# motion_sensor_circuit.net
KiCad netlist of a schematic drawn in Altium Designer
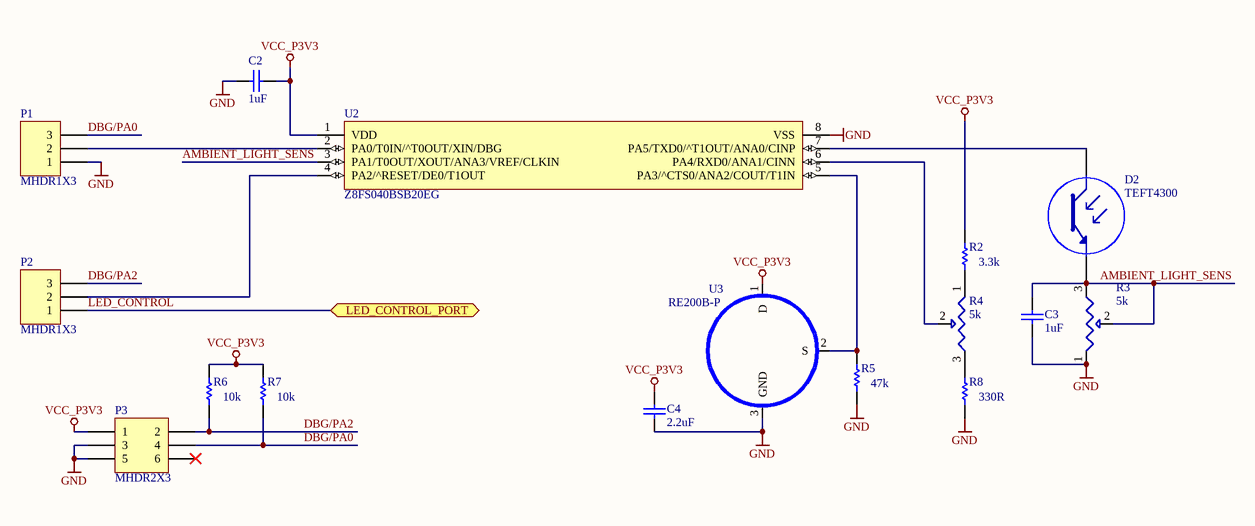
[diagram p0: motion sensor circuit.SchDoc]

(export (version "E")
  (design (tool "Eeschema 10.0.6"))
  (components
    (comp (ref "C2")
      (value "1uF")
      (footprint "1608[0603]")
      (description "Ceramic Chip Capacitor - Standard")
      (fields (field (name "Comment") "C0603C105K8PACTU") (field (name "PUBLISHER") "Altium Limited"))
      (libsource (lib "KEMET Chip Capacitor") (part "C0603"))
    )
    (comp (ref "C3")
      (value "1uF")
      (footprint "1608[0603]")
      (description "Ceramic Chip Capacitor - Standard")
      (fields (field (name "Comment") "C0603C105K8PACTU") (field (name "PUBLISHER") "Altium Limited"))
      (libsource (lib "KEMET Chip Capacitor") (part "C0603"))
    )
    (comp (ref "C4")
      (value "2.2uF")
      (footprint "1608[0603]")
      (description "Ceramic Chip Capacitor - Standard")
      (fields (field (name "Comment") "C0603C225K8PACTU") (field (name "PUBLISHER") "Altium Limited"))
      (libsource (lib "KEMET Chip Capacitor") (part "C0603"))
    )
    (comp (ref "D2")
      (value "TEFT4300")
      (footprint "LED")
      (description "Silicon NPN Phototransistor")
      (libsource (lib "Vishay Optoelectronics light sensors") (part "TEFT4300"))
    )
    (comp (ref "P1")
      (value "MHDR1X3")
      (footprint "MHDR1X3")
      (description "Header, 3-Pin")
      (fields (field (name "PUBLISHER") "Altium Limited"))
      (libsource (lib "Miscellaneous Connectors") (part "MHDR1X3"))
    )
    (comp (ref "P2")
      (value "MHDR1X3")
      (footprint "MHDR1X3")
      (description "Header, 3-Pin")
      (fields (field (name "PUBLISHER") "Altium Limited"))
      (libsource (lib "Miscellaneous Connectors") (part "MHDR1X3"))
    )
    (comp (ref "P3")
      (value "MHDR2X3")
      (footprint "MHDR2X3")
      (description "Header, 3-Pin, Dual row")
      (fields (field (name "PUBLISHER") "Altium Limited"))
      (libsource (lib "Miscellaneous Connectors") (part "MHDR2X3"))
    )
    (comp (ref "R2")
      (value "3.3k")
      (footprint "3-0603")
      (fields (field (name "Comment") "ERJ-3GEYJ332V") (field (name "PUBLISHER") "Altium Limited"))
      (libsource (lib "Panasonic Resistor") (part "ERJ3EK"))
    )
    (comp (ref "R3")
      (value "5k")
      (footprint "3386F")
      (description "3386 - 3/8 ” Square Trimpot Trimming Potentiometer")
      (fields (field (name "Comment") "3386F-1-502"))
      (libsource (lib "Bourns Variable Resistors") (part "3386F-1-XXX"))
    )
    (comp (ref "R4")
      (value "5k")
      (footprint "3386F")
      (description "3386 - 3/8 ” Square Trimpot Trimming Potentiometer")
      (fields (field (name "Comment") "3386F-1-502"))
      (libsource (lib "Bourns Variable Resistors") (part "3386F-1-XXX"))
    )
    (comp (ref "R5")
      (value "47k")
      (footprint "3-0603")
      (fields (field (name "Comment") "ERJ-3GEYJ473V") (field (name "PUBLISHER") "Altium Limited"))
      (libsource (lib "Panasonic Resistor") (part "ERJ3EK"))
    )
    (comp (ref "R6")
      (value "10k")
      (footprint "3-0603")
      (fields (field (name "Comment") "ERJ-3GEYJ103V") (field (name "PUBLISHER") "Altium Limited"))
      (libsource (lib "Panasonic Resistor") (part "ERJ3EK"))
    )
    (comp (ref "R7")
      (value "10k")
      (footprint "3-0603")
      (fields (field (name "Comment") "ERJ-3GEYJ103V") (field (name "PUBLISHER") "Altium Limited"))
      (libsource (lib "Panasonic Resistor") (part "ERJ3EK"))
    )
    (comp (ref "R8")
      (value "330R")
      (footprint "3-0603")
      (fields (field (name "Comment") "ERJ-3GEYJ331V") (field (name "PUBLISHER") "Altium Limited"))
      (libsource (lib "Panasonic Resistor") (part "ERJ3EK"))
    )
    (comp (ref "U2")
      (value "Z8FS040BSB20EG")
      (footprint "SOIC127P600X173-8N")
      (description "8-bit Microcontrollers - MCU ZMotion MCU Mot Det IC, 4KB Flash")
      (libsource (lib "Zilog Microcontroller 8-Bit") (part "Z8FS040BSB20EG"))
    )
    (comp (ref "U3")
      (value "RE200B-P")
      (footprint "RE200B-P")
      (description "Pyroelectric Passive Infrared Sensor")
      (libsource (lib "Rapid PIR sensors") (part "RE200B-P"))
    )
  )
  (nets
    (net (code "1") (name "/AMBIENT_LIGHT_SENS") (class "Default")
      (node (ref "C3") (pin "1") (pinfunction "1_1") (pintype "passive"))
      (node (ref "D2") (pin "2") (pintype "power_in"))
      (node (ref "R3") (pin "2") (pintype "power_in"))
      (node (ref "R3") (pin "3") (pinfunction "3_3") (pintype "power_in"))
      (node (ref "U2") (pin "3") (pinfunction "PA1/T0OUT/XOUT/ANA3/VREF/CLKIN_3") (pintype "bidirectional"))
    )
    (net (code "2") (name "/DBG{slash}PA0") (class "Default")
      (node (ref "P1") (pin "3") (pinfunction "3_3") (pintype "passive"))
      (node (ref "P3") (pin "4") (pinfunction "4_4") (pintype "passive"))
      (node (ref "R7") (pin "1") (pinfunction "1_1") (pintype "passive"))
    )
    (net (code "3") (name "/DBG{slash}PA2") (class "Default")
      (node (ref "P2") (pin "3") (pinfunction "3_3") (pintype "passive"))
      (node (ref "P3") (pin "2") (pinfunction "2_2") (pintype "passive"))
      (node (ref "R6") (pin "1") (pinfunction "1_1") (pintype "passive"))
    )
    (net (code "4") (name "/LED_CONTROL") (class "Default")
      (node (ref "P2") (pin "1") (pinfunction "1_1") (pintype "passive"))
    )
    (net (code "5") (name "GND") (class "Default")
      (node (ref "C2") (pin "2") (pinfunction "2_2") (pintype "passive"))
      (node (ref "C3") (pin "2") (pinfunction "2_2") (pintype "passive"))
      (node (ref "C4") (pin "2") (pinfunction "2_2") (pintype "passive"))
      (node (ref "P1") (pin "1") (pinfunction "1_1") (pintype "passive"))
      (node (ref "P3") (pin "3") (pinfunction "3_3") (pintype "passive"))
      (node (ref "P3") (pin "5") (pinfunction "5_5") (pintype "passive"))
      (node (ref "R3") (pin "1") (pintype "power_in"))
      (node (ref "R5") (pin "1") (pinfunction "1_1") (pintype "passive"))
      (node (ref "R8") (pin "1") (pinfunction "1_1") (pintype "passive"))
      (node (ref "U2") (pin "8") (pinfunction "VSS_8") (pintype "power_in"))
      (node (ref "U3") (pin "3") (pinfunction "GND_3") (pintype "power_in"))
    )
    (net (code "6") (name "Net-(R2-Pad1)") (class "Default")
      (node (ref "R2") (pin "1") (pinfunction "1_1") (pintype "passive"))
      (node (ref "R4") (pin "1") (pintype "power_in"))
    )
    (net (code "7") (name "Net-(R4-Pad3)") (class "Default")
      (node (ref "R4") (pin "3") (pinfunction "3_3") (pintype "power_in"))
      (node (ref "R8") (pin "2") (pinfunction "2_2") (pintype "passive"))
    )
    (net (code "8") (name "Net-(U2-PA0{slash}T0IN{slash}^T0OUT{slash}XIN{slash}DBG)") (class "Default")
      (node (ref "P1") (pin "2") (pinfunction "2_2") (pintype "passive"))
      (node (ref "U2") (pin "2") (pinfunction "PA0/T0IN/^T0OUT/XIN/DBG_2") (pintype "bidirectional"))
    )
    (net (code "9") (name "Net-(U2-PA2{slash}^RESET{slash}DE0{slash}T1OUT)") (class "Default")
      (node (ref "P2") (pin "2") (pinfunction "2_2") (pintype "passive"))
      (node (ref "U2") (pin "4") (pinfunction "PA2/^RESET/DE0/T1OUT_4") (pintype "bidirectional"))
    )
    (net (code "10") (name "Net-(U2-PA3{slash}^CTS0{slash}ANA2{slash}COUT{slash}T1IN)") (class "Default")
      (node (ref "R5") (pin "2") (pinfunction "2_2") (pintype "passive"))
      (node (ref "U2") (pin "5") (pinfunction "PA3/^CTS0/ANA2/COUT/T1IN_5") (pintype "bidirectional"))
      (node (ref "U3") (pin "2") (pinfunction "S_2") (pintype "power_in"))
    )
    (net (code "11") (name "Net-(U2-PA4{slash}RXD0{slash}ANA1{slash}CINN)") (class "Default")
      (node (ref "R4") (pin "2") (pintype "power_in"))
      (node (ref "U2") (pin "6") (pinfunction "PA4/RXD0/ANA1/CINN_6") (pintype "bidirectional"))
    )
    (net (code "12") (name "Net-(U2-PA5{slash}TXD0{slash}^T1OUT{slash}ANA0{slash}CINP)") (class "Default")
      (node (ref "D2") (pin "1") (pintype "power_in"))
      (node (ref "U2") (pin "7") (pinfunction "PA5/TXD0/^T1OUT/ANA0/CINP_7") (pintype "bidirectional"))
    )
    (net (code "13") (name "VCC_P3V3") (class "Default")
      (node (ref "C2") (pin "1") (pinfunction "1_1") (pintype "passive"))
      (node (ref "C4") (pin "1") (pinfunction "1_1") (pintype "passive"))
      (node (ref "P3") (pin "1") (pinfunction "1_1") (pintype "passive"))
      (node (ref "R2") (pin "2") (pinfunction "2_2") (pintype "passive"))
      (node (ref "R6") (pin "2") (pinfunction "2_2") (pintype "passive"))
      (node (ref "R7") (pin "2") (pinfunction "2_2") (pintype "passive"))
      (node (ref "U2") (pin "1") (pinfunction "VDD_1") (pintype "power_in"))
      (node (ref "U3") (pin "1") (pinfunction "D_1") (pintype "power_in"))
    )
    (net (code "14") (name "unconnected-(P3-Pad6)") (class "Default")
      (node (ref "P3") (pin "6") (pinfunction "6_6") (pintype "passive+no_connect"))
    )
  )
)
